# Side1.net
KiCad netlist of a schematic drawn in Altium Designer
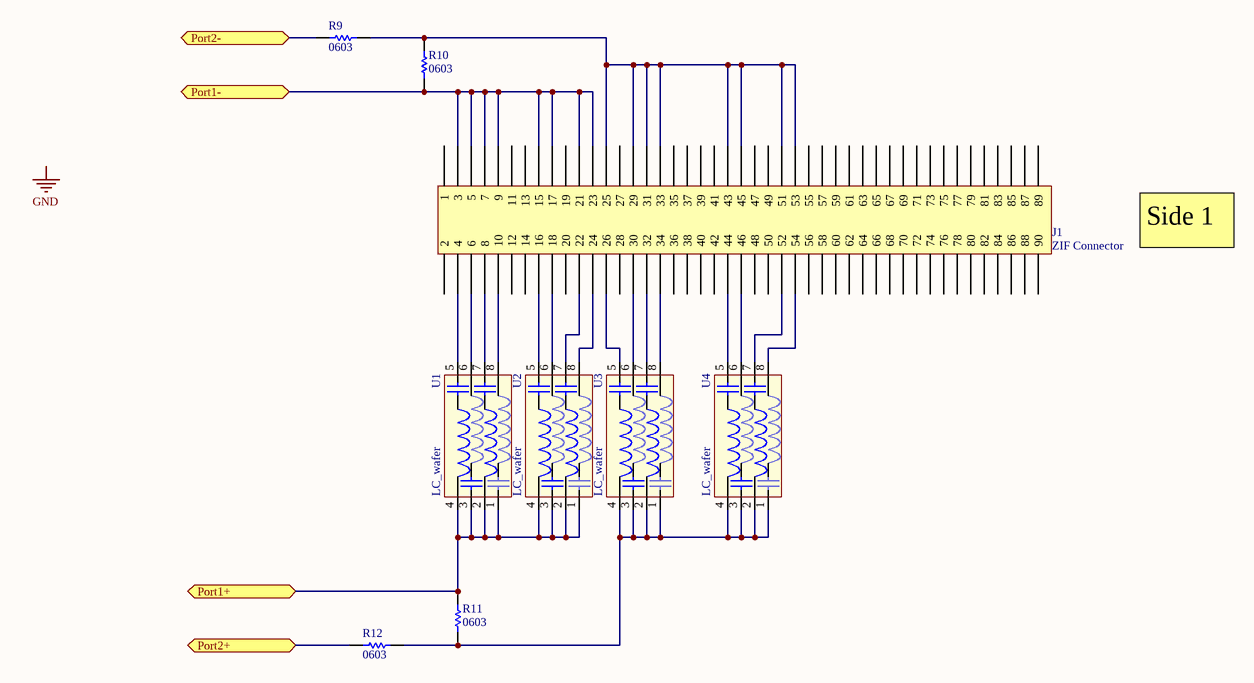
[diagram p0: Side1.SchDoc]

(export (version "E")
  (design (tool "Eeschema 10.0.6"))
  (components
    (comp (ref "J1")
      (value "ZIF Connector")
      (footprint "LCBoard_ZIFCon")
      (libsource (lib "altium-import") (part "root_1_LCboard_FH16-90S-0.3SHW(05)_"))
    )
    (comp (ref "R9")
      (value "0603")
      (footprint "0603")
      (description "RES 1 OHM 1/10W 1% 0603 SMD")
      (libsource (lib "LCboardPCB") (part "Res0603"))
    )
    (comp (ref "R10")
      (value "0603")
      (footprint "0603")
      (description "RES 1 OHM 1/10W 1% 0603 SMD")
      (libsource (lib "LCboardPCB") (part "Res0603"))
    )
    (comp (ref "R11")
      (value "0603")
      (footprint "0603")
      (description "RES 1 OHM 1/10W 1% 0603 SMD")
      (libsource (lib "LCboardPCB") (part "Res0603"))
    )
    (comp (ref "R12")
      (value "0603")
      (footprint "0603")
      (description "RES 1 OHM 1/10W 1% 0603 SMD")
      (libsource (lib "LCboardPCB") (part "Res0603"))
    )
    (comp (ref "U1")
      (value "LC_wafer")
      (footprint "LCWafer")
      (description "Gold bonded integrated LC")
      (libsource (lib "LCboardPCB") (part "LCWafer"))
    )
    (comp (ref "U2")
      (value "LC_wafer")
      (footprint "LCWafer")
      (description "Gold bonded integrated LC")
      (libsource (lib "LCboardPCB") (part "LCWafer"))
    )
    (comp (ref "U3")
      (value "LC_wafer")
      (footprint "LCWafer")
      (description "Gold bonded integrated LC")
      (libsource (lib "LCboardPCB") (part "LCWafer"))
    )
    (comp (ref "U4")
      (value "LC_wafer")
      (footprint "LCWafer")
      (description "Gold bonded integrated LC")
      (libsource (lib "LCboardPCB") (part "LCWafer"))
    )
  )
  (nets
    (net (code "1") (name "/Port1+") (class "Default")
      (node (ref "R11") (pin "2") (pinfunction "2_2") (pintype "passive"))
      (node (ref "U1") (pin "1") (pinfunction "1_1") (pintype "passive"))
      (node (ref "U1") (pin "2") (pinfunction "2_2") (pintype "passive"))
      (node (ref "U1") (pin "3") (pinfunction "3_3") (pintype "passive"))
      (node (ref "U1") (pin "4") (pinfunction "4_4") (pintype "passive"))
      (node (ref "U2") (pin "1") (pinfunction "1_1") (pintype "passive"))
      (node (ref "U2") (pin "2") (pinfunction "2_2") (pintype "passive"))
      (node (ref "U2") (pin "3") (pinfunction "3_3") (pintype "passive"))
      (node (ref "U2") (pin "4") (pinfunction "4_4") (pintype "passive"))
    )
    (net (code "2") (name "/Port1-") (class "Default")
      (node (ref "J1") (pin "15") (pinfunction "15_15") (pintype "passive"))
      (node (ref "J1") (pin "17") (pinfunction "17_17") (pintype "passive"))
      (node (ref "J1") (pin "21") (pinfunction "21_21") (pintype "passive"))
      (node (ref "J1") (pin "23") (pinfunction "23_23") (pintype "passive"))
      (node (ref "J1") (pin "3") (pinfunction "3_3") (pintype "passive"))
      (node (ref "J1") (pin "5") (pinfunction "5_5") (pintype "passive"))
      (node (ref "J1") (pin "7") (pinfunction "7_7") (pintype "passive"))
      (node (ref "J1") (pin "9") (pinfunction "9_9") (pintype "passive"))
      (node (ref "R10") (pin "1") (pinfunction "1_1") (pintype "passive"))
    )
    (net (code "3") (name "/Port2+") (class "Default")
      (node (ref "R12") (pin "2") (pinfunction "2_2") (pintype "passive"))
    )
    (net (code "4") (name "/Port2-") (class "Default")
      (node (ref "R9") (pin "2") (pinfunction "2_2") (pintype "passive"))
    )
    (net (code "6") (name "Net-(J1-Pad4)") (class "Default")
      (node (ref "J1") (pin "4") (pinfunction "4_4") (pintype "passive"))
      (node (ref "U1") (pin "5") (pinfunction "5_5") (pintype "passive"))
    )
    (net (code "7") (name "Net-(J1-Pad6)") (class "Default")
      (node (ref "J1") (pin "6") (pinfunction "6_6") (pintype "passive"))
      (node (ref "U1") (pin "6") (pinfunction "6_6") (pintype "passive"))
    )
    (net (code "8") (name "Net-(J1-Pad8)") (class "Default")
      (node (ref "J1") (pin "8") (pinfunction "8_8") (pintype "passive"))
      (node (ref "U1") (pin "7") (pinfunction "7_7") (pintype "passive"))
    )
    (net (code "9") (name "Net-(J1-Pad10)") (class "Default")
      (node (ref "J1") (pin "10") (pinfunction "10_10") (pintype "passive"))
      (node (ref "U1") (pin "8") (pinfunction "8_8") (pintype "passive"))
    )
    (net (code "10") (name "Net-(J1-Pad16)") (class "Default")
      (node (ref "J1") (pin "16") (pinfunction "16_16") (pintype "passive"))
      (node (ref "U2") (pin "5") (pinfunction "5_5") (pintype "passive"))
    )
    (net (code "11") (name "Net-(J1-Pad18)") (class "Default")
      (node (ref "J1") (pin "18") (pinfunction "18_18") (pintype "passive"))
      (node (ref "U2") (pin "6") (pinfunction "6_6") (pintype "passive"))
    )
    (net (code "12") (name "Net-(J1-Pad22)") (class "Default")
      (node (ref "J1") (pin "22") (pinfunction "22_22") (pintype "passive"))
      (node (ref "U2") (pin "7") (pinfunction "7_7") (pintype "passive"))
    )
    (net (code "13") (name "Net-(J1-Pad24)") (class "Default")
      (node (ref "J1") (pin "24") (pinfunction "24_24") (pintype "passive"))
      (node (ref "U2") (pin "8") (pinfunction "8_8") (pintype "passive"))
    )
    (net (code "14") (name "Net-(J1-Pad25)") (class "Default")
      (node (ref "J1") (pin "25") (pinfunction "25_25") (pintype "passive"))
      (node (ref "J1") (pin "29") (pinfunction "29_29") (pintype "passive"))
      (node (ref "J1") (pin "31") (pinfunction "31_31") (pintype "passive"))
      (node (ref "J1") (pin "33") (pinfunction "33_33") (pintype "passive"))
      (node (ref "J1") (pin "43") (pinfunction "43_43") (pintype "passive"))
      (node (ref "J1") (pin "45") (pinfunction "45_45") (pintype "passive"))
      (node (ref "J1") (pin "51") (pinfunction "51_51") (pintype "passive"))
      (node (ref "J1") (pin "53") (pinfunction "53_53") (pintype "passive"))
      (node (ref "R10") (pin "2") (pinfunction "2_2") (pintype "passive"))
      (node (ref "R9") (pin "1") (pinfunction "1_1") (pintype "passive"))
    )
    (net (code "15") (name "Net-(J1-Pad26)") (class "Default")
      (node (ref "J1") (pin "26") (pinfunction "26_26") (pintype "passive"))
      (node (ref "U3") (pin "5") (pinfunction "5_5") (pintype "passive"))
    )
    (net (code "16") (name "Net-(J1-Pad30)") (class "Default")
      (node (ref "J1") (pin "30") (pinfunction "30_30") (pintype "passive"))
      (node (ref "U3") (pin "6") (pinfunction "6_6") (pintype "passive"))
    )
    (net (code "17") (name "Net-(J1-Pad32)") (class "Default")
      (node (ref "J1") (pin "32") (pinfunction "32_32") (pintype "passive"))
      (node (ref "U3") (pin "7") (pinfunction "7_7") (pintype "passive"))
    )
    (net (code "18") (name "Net-(J1-Pad34)") (class "Default")
      (node (ref "J1") (pin "34") (pinfunction "34_34") (pintype "passive"))
      (node (ref "U3") (pin "8") (pinfunction "8_8") (pintype "passive"))
    )
    (net (code "19") (name "Net-(J1-Pad44)") (class "Default")
      (node (ref "J1") (pin "44") (pinfunction "44_44") (pintype "passive"))
      (node (ref "U4") (pin "5") (pinfunction "5_5") (pintype "passive"))
    )
    (net (code "20") (name "Net-(J1-Pad46)") (class "Default")
      (node (ref "J1") (pin "46") (pinfunction "46_46") (pintype "passive"))
      (node (ref "U4") (pin "6") (pinfunction "6_6") (pintype "passive"))
    )
    (net (code "21") (name "Net-(J1-Pad52)") (class "Default")
      (node (ref "J1") (pin "52") (pinfunction "52_52") (pintype "passive"))
      (node (ref "U4") (pin "7") (pinfunction "7_7") (pintype "passive"))
    )
    (net (code "22") (name "Net-(J1-Pad54)") (class "Default")
      (node (ref "J1") (pin "54") (pinfunction "54_54") (pintype "passive"))
      (node (ref "U4") (pin "8") (pinfunction "8_8") (pintype "passive"))
    )
    (net (code "23") (name "Net-(R11-Pad1)") (class "Default")
      (node (ref "R11") (pin "1") (pinfunction "1_1") (pintype "passive"))
      (node (ref "R12") (pin "1") (pinfunction "1_1") (pintype "passive"))
      (node (ref "U3") (pin "1") (pinfunction "1_1") (pintype "passive"))
      (node (ref "U3") (pin "2") (pinfunction "2_2") (pintype "passive"))
      (node (ref "U3") (pin "3") (pinfunction "3_3") (pintype "passive"))
      (node (ref "U3") (pin "4") (pinfunction "4_4") (pintype "passive"))
      (node (ref "U4") (pin "1") (pinfunction "1_1") (pintype "passive"))
      (node (ref "U4") (pin "2") (pinfunction "2_2") (pintype "passive"))
      (node (ref "U4") (pin "3") (pinfunction "3_3") (pintype "passive"))
      (node (ref "U4") (pin "4") (pinfunction "4_4") (pintype "passive"))
    )
    (net (code "24") (name "unconnected-(J1-Pad1)") (class "Default")
      (node (ref "J1") (pin "1") (pinfunction "1_1") (pintype "passive"))
    )
    (net (code "25") (name "unconnected-(J1-Pad2)") (class "Default")
      (node (ref "J1") (pin "2") (pinfunction "2_2") (pintype "passive"))
    )
    (net (code "26") (name "unconnected-(J1-Pad11)") (class "Default")
      (node (ref "J1") (pin "11") (pinfunction "11_11") (pintype "passive"))
    )
    (net (code "27") (name "unconnected-(J1-Pad12)") (class "Default")
      (node (ref "J1") (pin "12") (pinfunction "12_12") (pintype "passive"))
    )
    (net (code "28") (name "unconnected-(J1-Pad13)") (class "Default")
      (node (ref "J1") (pin "13") (pinfunction "13_13") (pintype "passive"))
    )
    (net (code "29") (name "unconnected-(J1-Pad14)") (class "Default")
      (node (ref "J1") (pin "14") (pinfunction "14_14") (pintype "passive"))
    )
    (net (code "30") (name "unconnected-(J1-Pad19)") (class "Default")
      (node (ref "J1") (pin "19") (pinfunction "19_19") (pintype "passive"))
    )
    (net (code "31") (name "unconnected-(J1-Pad20)") (class "Default")
      (node (ref "J1") (pin "20") (pinfunction "20_20") (pintype "passive"))
    )
    (net (code "32") (name "unconnected-(J1-Pad27)") (class "Default")
      (node (ref "J1") (pin "27") (pinfunction "27_27") (pintype "passive"))
    )
    (net (code "33") (name "unconnected-(J1-Pad28)") (class "Default")
      (node (ref "J1") (pin "28") (pinfunction "28_28") (pintype "passive"))
    )
    (net (code "34") (name "unconnected-(J1-Pad35)") (class "Default")
      (node (ref "J1") (pin "35") (pinfunction "35_35") (pintype "passive"))
    )
    (net (code "35") (name "unconnected-(J1-Pad36)") (class "Default")
      (node (ref "J1") (pin "36") (pinfunction "36_36") (pintype "passive"))
    )
    (net (code "36") (name "unconnected-(J1-Pad37)") (class "Default")
      (node (ref "J1") (pin "37") (pinfunction "37_37") (pintype "passive"))
    )
    (net (code "37") (name "unconnected-(J1-Pad38)") (class "Default")
      (node (ref "J1") (pin "38") (pinfunction "38_38") (pintype "passive"))
    )
    (net (code "38") (name "unconnected-(J1-Pad39)") (class "Default")
      (node (ref "J1") (pin "39") (pinfunction "39_39") (pintype "passive"))
    )
    (net (code "39") (name "unconnected-(J1-Pad40)") (class "Default")
      (node (ref "J1") (pin "40") (pinfunction "40_40") (pintype "passive"))
    )
    (net (code "40") (name "unconnected-(J1-Pad41)") (class "Default")
      (node (ref "J1") (pin "41") (pinfunction "41_41") (pintype "passive"))
    )
    (net (code "41") (name "unconnected-(J1-Pad42)") (class "Default")
      (node (ref "J1") (pin "42") (pinfunction "42_42") (pintype "passive"))
    )
    (net (code "42") (name "unconnected-(J1-Pad47)") (class "Default")
      (node (ref "J1") (pin "47") (pinfunction "47_47") (pintype "passive"))
    )
    (net (code "43") (name "unconnected-(J1-Pad48)") (class "Default")
      (node (ref "J1") (pin "48") (pinfunction "48_48") (pintype "passive"))
    )
    (net (code "44") (name "unconnected-(J1-Pad49)") (class "Default")
      (node (ref "J1") (pin "49") (pinfunction "49_49") (pintype "passive"))
    )
    (net (code "45") (name "unconnected-(J1-Pad50)") (class "Default")
      (node (ref "J1") (pin "50") (pinfunction "50_50") (pintype "passive"))
    )
    (net (code "46") (name "unconnected-(J1-Pad55)") (class "Default")
      (node (ref "J1") (pin "55") (pinfunction "55_55") (pintype "passive"))
    )
    (net (code "47") (name "unconnected-(J1-Pad56)") (class "Default")
      (node (ref "J1") (pin "56") (pinfunction "56_56") (pintype "passive"))
    )
    (net (code "48") (name "unconnected-(J1-Pad57)") (class "Default")
      (node (ref "J1") (pin "57") (pinfunction "57_57") (pintype "passive"))
    )
    (net (code "49") (name "unconnected-(J1-Pad58)") (class "Default")
      (node (ref "J1") (pin "58") (pinfunction "58_58") (pintype "passive"))
    )
    (net (code "50") (name "unconnected-(J1-Pad59)") (class "Default")
      (node (ref "J1") (pin "59") (pinfunction "59_59") (pintype "passive"))
    )
    (net (code "51") (name "unconnected-(J1-Pad60)") (class "Default")
      (node (ref "J1") (pin "60") (pinfunction "60_60") (pintype "passive"))
    )
    (net (code "52") (name "unconnected-(J1-Pad61)") (class "Default")
      (node (ref "J1") (pin "61") (pinfunction "61_61") (pintype "passive"))
    )
    (net (code "53") (name "unconnected-(J1-Pad62)") (class "Default")
      (node (ref "J1") (pin "62") (pinfunction "62_62") (pintype "passive"))
    )
    (net (code "54") (name "unconnected-(J1-Pad63)") (class "Default")
      (node (ref "J1") (pin "63") (pinfunction "63_63") (pintype "passive"))
    )
    (net (code "55") (name "unconnected-(J1-Pad64)") (class "Default")
      (node (ref "J1") (pin "64") (pinfunction "64_64") (pintype "passive"))
    )
    (net (code "56") (name "unconnected-(J1-Pad65)") (class "Default")
      (node (ref "J1") (pin "65") (pinfunction "65_65") (pintype "passive"))
    )
    (net (code "57") (name "unconnected-(J1-Pad66)") (class "Default")
      (node (ref "J1") (pin "66") (pinfunction "66_66") (pintype "passive"))
    )
    (net (code "58") (name "unconnected-(J1-Pad67)") (class "Default")
      (node (ref "J1") (pin "67") (pinfunction "67_67") (pintype "passive"))
    )
    (net (code "59") (name "unconnected-(J1-Pad68)") (class "Default")
      (node (ref "J1") (pin "68") (pinfunction "68_68") (pintype "passive"))
    )
    (net (code "60") (name "unconnected-(J1-Pad69)") (class "Default")
      (node (ref "J1") (pin "69") (pinfunction "69_69") (pintype "passive"))
    )
    (net (code "61") (name "unconnected-(J1-Pad70)") (class "Default")
      (node (ref "J1") (pin "70") (pinfunction "70_70") (pintype "passive"))
    )
    (net (code "62") (name "unconnected-(J1-Pad71)") (class "Default")
      (node (ref "J1") (pin "71") (pinfunction "71_71") (pintype "passive"))
    )
    (net (code "63") (name "unconnected-(J1-Pad72)") (class "Default")
      (node (ref "J1") (pin "72") (pinfunction "72_72") (pintype "passive"))
    )
    (net (code "64") (name "unconnected-(J1-Pad73)") (class "Default")
      (node (ref "J1") (pin "73") (pinfunction "73_73") (pintype "passive"))
    )
    (net (code "65") (name "unconnected-(J1-Pad74)") (class "Default")
      (node (ref "J1") (pin "74") (pinfunction "74_74") (pintype "passive"))
    )
    (net (code "66") (name "unconnected-(J1-Pad75)") (class "Default")
      (node (ref "J1") (pin "75") (pinfunction "75_75") (pintype "passive"))
    )
    (net (code "67") (name "unconnected-(J1-Pad76)") (class "Default")
      (node (ref "J1") (pin "76") (pinfunction "76_76") (pintype "passive"))
    )
    (net (code "68") (name "unconnected-(J1-Pad77)") (class "Default")
      (node (ref "J1") (pin "77") (pinfunction "77_77") (pintype "passive"))
    )
    (net (code "69") (name "unconnected-(J1-Pad78)") (class "Default")
      (node (ref "J1") (pin "78") (pinfunction "78_78") (pintype "passive"))
    )
    (net (code "70") (name "unconnected-(J1-Pad79)") (class "Default")
      (node (ref "J1") (pin "79") (pinfunction "79_79") (pintype "passive"))
    )
    (net (code "71") (name "unconnected-(J1-Pad80)") (class "Default")
      (node (ref "J1") (pin "80") (pinfunction "80_80") (pintype "passive"))
    )
    (net (code "72") (name "unconnected-(J1-Pad81)") (class "Default")
      (node (ref "J1") (pin "81") (pinfunction "81_81") (pintype "passive"))
    )
    (net (code "73") (name "unconnected-(J1-Pad82)") (class "Default")
      (node (ref "J1") (pin "82") (pinfunction "82_82") (pintype "passive"))
    )
    (net (code "74") (name "unconnected-(J1-Pad83)") (class "Default")
      (node (ref "J1") (pin "83") (pinfunction "83_83") (pintype "passive"))
    )
    (net (code "75") (name "unconnected-(J1-Pad84)") (class "Default")
      (node (ref "J1") (pin "84") (pinfunction "84_84") (pintype "passive"))
    )
    (net (code "76") (name "unconnected-(J1-Pad85)") (class "Default")
      (node (ref "J1") (pin "85") (pinfunction "85_85") (pintype "passive"))
    )
    (net (code "77") (name "unconnected-(J1-Pad86)") (class "Default")
      (node (ref "J1") (pin "86") (pinfunction "86_86") (pintype "passive"))
    )
    (net (code "78") (name "unconnected-(J1-Pad87)") (class "Default")
      (node (ref "J1") (pin "87") (pinfunction "87_87") (pintype "passive"))
    )
    (net (code "79") (name "unconnected-(J1-Pad88)") (class "Default")
      (node (ref "J1") (pin "88") (pinfunction "88_88") (pintype "passive"))
    )
    (net (code "80") (name "unconnected-(J1-Pad89)") (class "Default")
      (node (ref "J1") (pin "89") (pinfunction "89_89") (pintype "passive"))
    )
    (net (code "81") (name "unconnected-(J1-Pad90)") (class "Default")
      (node (ref "J1") (pin "90") (pinfunction "90_90") (pintype "passive"))
    )
  )
)
